# SCH_ODO_2025-04-28_1.net
KiCad netlist of a schematic drawn in EasyEDA
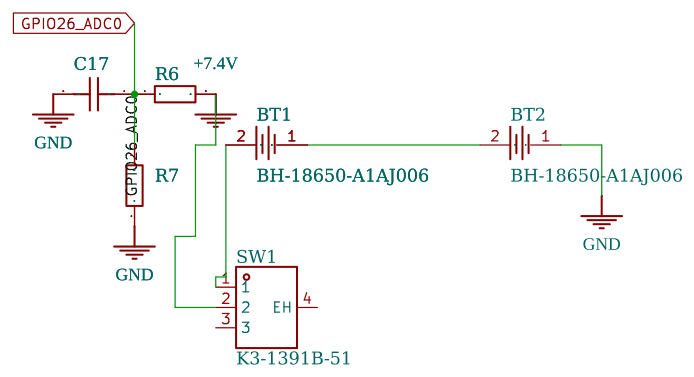
[diagram p0: schematic sheet]

(export (version "E")
  (design (tool "Eeschema 10.0.6"))
  (components
    (comp (ref "BT1")
      (value "BH-18650-A1AJ006")
      (fields (field (name "Manufacturer") "MYOUNG(美阳)"))
      (libsource (lib "") (part "Unknown_230_-645"))
    )
    (comp (ref "BT2")
      (value "BH-18650-A1AJ006")
      (fields (field (name "Manufacturer") "MYOUNG(美阳)"))
      (libsource (lib "") (part "Unknown_355_-645"))
    )
    (comp (ref "C17") (value "100nF") (libsource (lib "") (part "Unknown_145_-670")))
    (comp (ref "R6") (value "18K") (libsource (lib "") (part "Unknown_185_-670")))
    (comp (ref "R7") (value "10K") (libsource (lib "") (part "Unknown_165_-625")))
    (comp (ref "SW1")
      (value "K3-1391B-51")
      (fields (field (name "Manufacturer") "韩国韩荣"))
      (libsource (lib "") (part "Unknown_230_-565"))
    )
  )
  (nets
    (net (code "1") (name "+7.4V") (class "Default")
      (node (ref "R6") (pin "2") (pinfunction "2_2") (pintype "unspecified"))
      (node (ref "SW1") (pin "2") (pinfunction "2_2") (pintype "unspecified"))
    )
    (net (code "2") (name "GND") (class "Default")
      (node (ref "BT2") (pin "1") (pinfunction "1_1") (pintype "unspecified"))
      (node (ref "C17") (pin "2") (pinfunction "2_2") (pintype "unspecified"))
      (node (ref "R7") (pin "1") (pinfunction "1_1") (pintype "unspecified"))
    )
    (net (code "3") (name "GPIO26_ADC0") (class "Default")
      (node (ref "C17") (pin "1") (pinfunction "1_1") (pintype "unspecified"))
      (node (ref "R6") (pin "1") (pinfunction "1_1") (pintype "unspecified"))
      (node (ref "R7") (pin "2") (pinfunction "2_2") (pintype "unspecified"))
    )
    (net (code "4") (name "Net-(BT1-Pad1)") (class "Default")
      (node (ref "BT1") (pin "1") (pinfunction "1_1") (pintype "unspecified"))
      (node (ref "BT2") (pin "2") (pinfunction "2_2") (pintype "unspecified"))
    )
    (net (code "5") (name "Net-(BT1-Pad2)") (class "Default")
      (node (ref "BT1") (pin "2") (pinfunction "2_2") (pintype "unspecified"))
      (node (ref "SW1") (pin "1") (pinfunction "1_1") (pintype "unspecified"))
    )
    (net (code "6") (name "unconnected-(SW1-EH-Pad4)") (class "Default")
      (node (ref "SW1") (pin "4") (pinfunction "EH_4") (pintype "unspecified"))
    )
    (net (code "7") (name "unconnected-(SW1-Pad3)") (class "Default")
      (node (ref "SW1") (pin "3") (pinfunction "3_3") (pintype "unspecified"))
    )
  )
)
